# Heater.net
KiCad netlist of a schematic drawn in Altium Designer
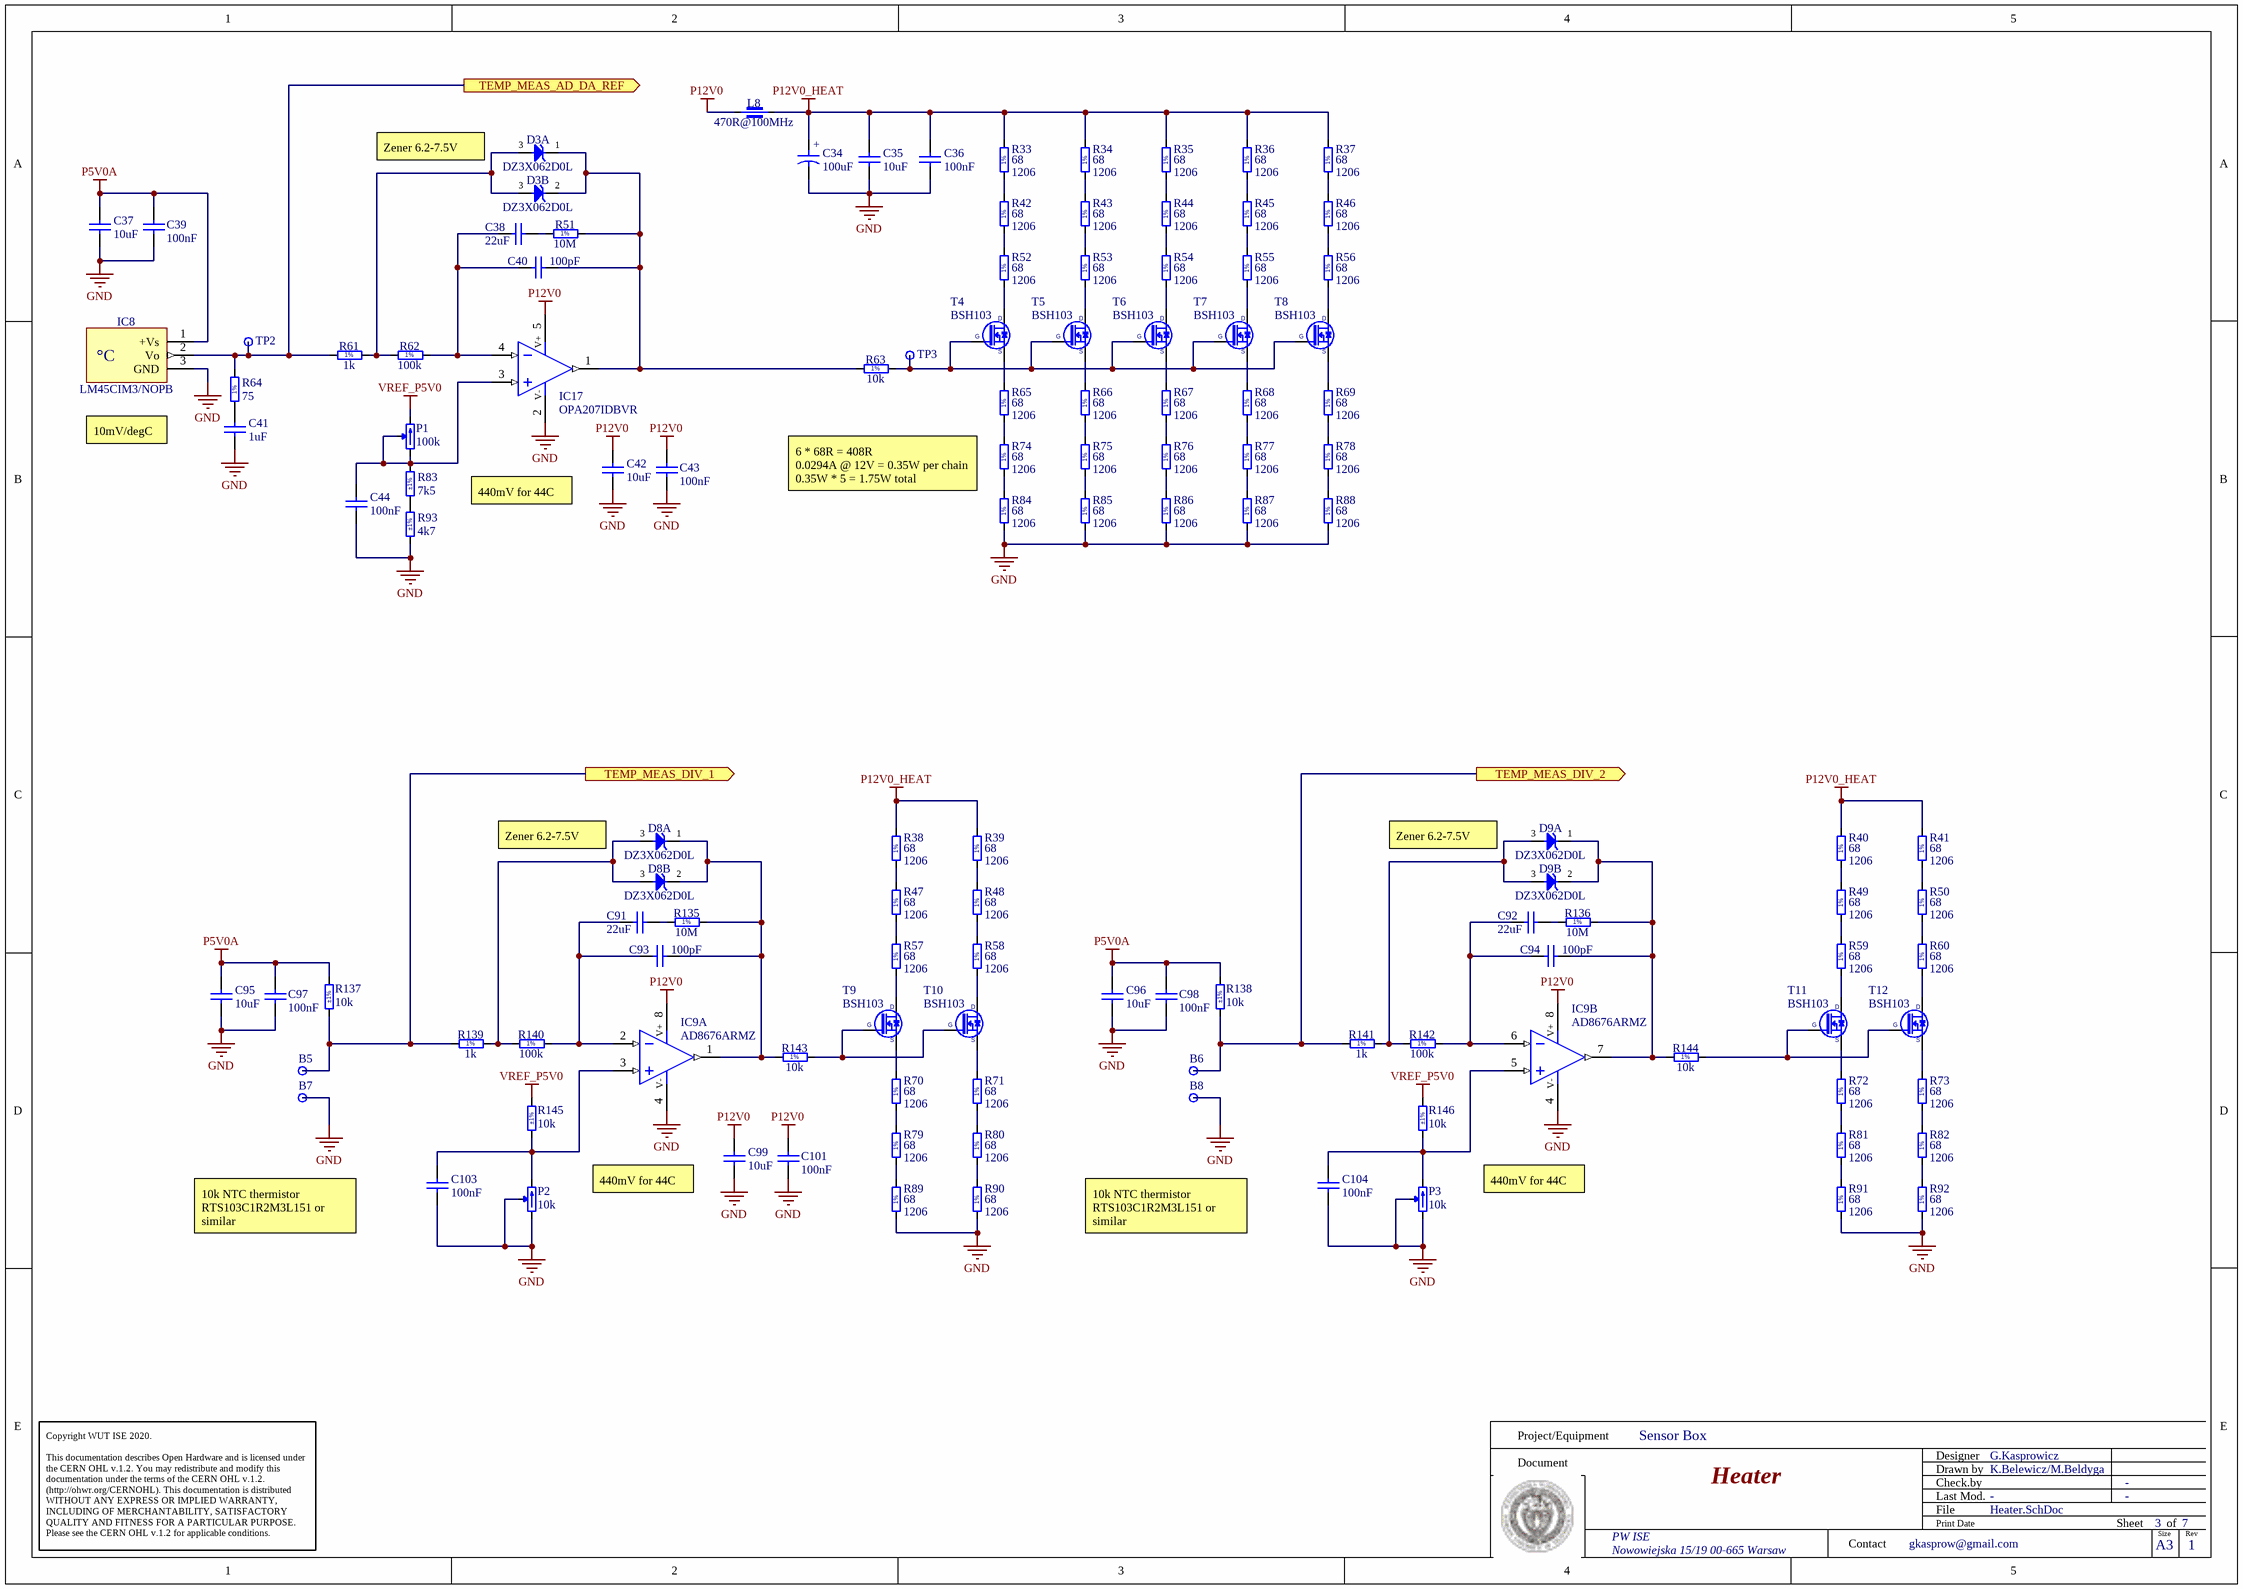
[diagram p0: Heater.SchDoc]

(export (version "E")
  (design (tool "Eeschema 10.0.6"))
  (components
    (comp (ref "B5")
      (value "Plated Hole")
      (footprint "c150h80")
      (description "Single Terminal Socket")
      (fields (field (name "PART NUMBER") "PLATED_HOLE0.8_PAD1.5") (field (name "AUTHOR") "CERN DEM JLC"))
      (libsource (lib "Eletro-mechanical") (part "Single Terminal Socket"))
    )
    (comp (ref "B6")
      (value "Plated Hole")
      (footprint "c150h80")
      (description "Single Terminal Socket")
      (fields (field (name "PART NUMBER") "PLATED_HOLE0.8_PAD1.5") (field (name "AUTHOR") "CERN DEM JLC"))
      (libsource (lib "Eletro-mechanical") (part "Single Terminal Socket"))
    )
    (comp (ref "B7")
      (value "Plated Hole")
      (footprint "c150h80")
      (description "Single Terminal Socket")
      (fields (field (name "PART NUMBER") "PLATED_HOLE0.8_PAD1.5") (field (name "AUTHOR") "CERN DEM JLC"))
      (libsource (lib "Eletro-mechanical") (part "Single Terminal Socket"))
    )
    (comp (ref "B8")
      (value "Plated Hole")
      (footprint "c150h80")
      (description "Single Terminal Socket")
      (fields (field (name "PART NUMBER") "PLATED_HOLE0.8_PAD1.5") (field (name "AUTHOR") "CERN DEM JLC"))
      (libsource (lib "Eletro-mechanical") (part "Single Terminal Socket"))
    )
    (comp (ref "C34")
      (value "100uF")
      (footprint "CAPMP7343X310N")
      (description "Polarised capacitor")
      (fields
        (field (name "PART NUMBER") "CTE7343-31_100UF_20V_10%")
        (field (name "VOLTAGE") "20V")
        (field (name "AUTHOR") "CERN DEM JLC")
      )
      (libsource (lib "Capacitors") (part "Capacitor - polarized"))
    )
    (comp (ref "C35")
      (value "10uF")
      (footprint "CAPC1608X80N")
      (description "Non-polarised capacitor")
      (fields
        (field (name "PART NUMBER") "CC0603_10UF_10V_10%_X5R")
        (field (name "VOLTAGE") "10V")
        (field (name "AUTHOR") "CERN DEM JLC")
      )
      (libsource (lib "Capacitors") (part "Capacitor - non polarized"))
    )
    (comp (ref "C36")
      (value "100nF")
      (footprint "CAPC1005X55N")
      (description "Non-polarised capacitor")
      (fields
        (field (name "PART NUMBER") "CC0402_100NF_16V_10%_X5R")
        (field (name "VOLTAGE") "16V")
        (field (name "AUTHOR") "CERN DEM JLC")
      )
      (libsource (lib "Capacitors") (part "Capacitor - non polarized"))
    )
    (comp (ref "C37")
      (value "10uF")
      (footprint "CAPC1608X80N")
      (description "Non-polarised capacitor")
      (fields
        (field (name "PART NUMBER") "CC0603_10UF_10V_10%_X5R")
        (field (name "VOLTAGE") "10V")
        (field (name "AUTHOR") "CERN DEM JLC")
      )
      (libsource (lib "Capacitors") (part "Capacitor - non polarized"))
    )
    (comp (ref "C38")
      (value "22uF")
      (footprint "CAPC2012X135N")
      (description "Non-polarised capacitor")
      (fields
        (field (name "MANUFACTURER PART NUMBER") "CC0805_22UF_16V_10%_X5R")
        (field (name "MANUFACTURER") "GENERIC")
        (field (name "AUTHOR") "CERN DEM JLC")
      )
      (libsource (lib "Capacitors") (part "Capacitor - non polarized"))
    )
    (comp (ref "C39")
      (value "100nF")
      (footprint "CAPC1005X55N")
      (description "Non-polarised capacitor")
      (fields
        (field (name "PART NUMBER") "CC0402_100NF_50V_10%_X7R")
        (field (name "VOLTAGE") "50V")
        (field (name "AUTHOR") "CERN DEM MR")
      )
      (libsource (lib "Capacitors") (part "Capacitor - non polarized"))
    )
    (comp (ref "C40")
      (value "100pF")
      (footprint "CAPC1005X55N")
      (description "Non-polarised capacitor")
      (fields
        (field (name "PART NUMBER") "CC0402_100PF_50V_5%_C0G")
        (field (name "VOLTAGE") "50V")
        (field (name "AUTHOR") "CERN DEM JLC")
      )
      (libsource (lib "Capacitors") (part "Capacitor - non polarized"))
    )
    (comp (ref "C41")
      (value "1uF")
      (footprint "CAPC1005X55N")
      (description "Non-polarised capacitor")
      (fields
        (field (name "PART NUMBER") "CC0402_1UF_16V_10%_X5R")
        (field (name "VOLTAGE") "16V")
        (field (name "AUTHOR") "CERN DEM JLC")
      )
      (libsource (lib "Capacitors") (part "Capacitor - non polarized"))
    )
    (comp (ref "C42")
      (value "10uF")
      (footprint "CAPC1608X80N")
      (description "Non-polarised capacitor")
      (fields
        (field (name "PART NUMBER") "CC0603_10UF_10V_10%_X5R")
        (field (name "VOLTAGE") "10V")
        (field (name "AUTHOR") "CERN DEM JLC")
      )
      (libsource (lib "Capacitors") (part "Capacitor - non polarized"))
    )
    (comp (ref "C43")
      (value "100nF")
      (footprint "CAPC1005X55N")
      (description "Non-polarised capacitor")
      (fields
        (field (name "PART NUMBER") "CC0402_100NF_50V_10%_X7R")
        (field (name "VOLTAGE") "50V")
        (field (name "AUTHOR") "CERN DEM MR")
      )
      (libsource (lib "Capacitors") (part "Capacitor - non polarized"))
    )
    (comp (ref "C44")
      (value "100nF")
      (footprint "CAPC1005X55N")
      (description "Non-polarised capacitor")
      (fields
        (field (name "PART NUMBER") "CC0402_100NF_16V_10%_X5R")
        (field (name "VOLTAGE") "16V")
        (field (name "AUTHOR") "CERN DEM JLC")
      )
      (libsource (lib "Capacitors") (part "Capacitor - non polarized"))
    )
    (comp (ref "C91")
      (value "22uF")
      (footprint "CAPC2012X135N")
      (description "Non-polarised capacitor")
      (fields
        (field (name "MANUFACTURER PART NUMBER") "CC0805_22UF_16V_10%_X5R")
        (field (name "MANUFACTURER") "GENERIC")
        (field (name "AUTHOR") "CERN DEM JLC")
      )
      (libsource (lib "Capacitors") (part "Capacitor - non polarized"))
    )
    (comp (ref "C92")
      (value "22uF")
      (footprint "CAPC2012X135N")
      (description "Non-polarised capacitor")
      (fields
        (field (name "MANUFACTURER PART NUMBER") "CC0805_22UF_16V_10%_X5R")
        (field (name "MANUFACTURER") "GENERIC")
        (field (name "AUTHOR") "CERN DEM JLC")
      )
      (libsource (lib "Capacitors") (part "Capacitor - non polarized"))
    )
    (comp (ref "C93")
      (value "100pF")
      (footprint "CAPC1005X55N")
      (description "Non-polarised capacitor")
      (fields
        (field (name "PART NUMBER") "CC0402_100PF_50V_5%_C0G")
        (field (name "VOLTAGE") "50V")
        (field (name "AUTHOR") "CERN DEM JLC")
      )
      (libsource (lib "Capacitors") (part "Capacitor - non polarized"))
    )
    (comp (ref "C94")
      (value "100pF")
      (footprint "CAPC1005X55N")
      (description "Non-polarised capacitor")
      (fields
        (field (name "PART NUMBER") "CC0402_100PF_50V_5%_C0G")
        (field (name "VOLTAGE") "50V")
        (field (name "AUTHOR") "CERN DEM JLC")
      )
      (libsource (lib "Capacitors") (part "Capacitor - non polarized"))
    )
    (comp (ref "C95")
      (value "10uF")
      (footprint "CAPC1608X80N")
      (description "Non-polarised capacitor")
      (fields
        (field (name "PART NUMBER") "CC0603_10UF_10V_10%_X5R")
        (field (name "VOLTAGE") "10V")
        (field (name "AUTHOR") "CERN DEM JLC")
      )
      (libsource (lib "Capacitors") (part "Capacitor - non polarized"))
    )
    (comp (ref "C96")
      (value "10uF")
      (footprint "CAPC1608X80N")
      (description "Non-polarised capacitor")
      (fields
        (field (name "PART NUMBER") "CC0603_10UF_10V_10%_X5R")
        (field (name "VOLTAGE") "10V")
        (field (name "AUTHOR") "CERN DEM JLC")
      )
      (libsource (lib "Capacitors") (part "Capacitor - non polarized"))
    )
    (comp (ref "C97")
      (value "100nF")
      (footprint "CAPC1005X55N")
      (description "Non-polarised capacitor")
      (fields
        (field (name "PART NUMBER") "CC0402_100NF_50V_10%_X7R")
        (field (name "VOLTAGE") "50V")
        (field (name "AUTHOR") "CERN DEM MR")
      )
      (libsource (lib "Capacitors") (part "Capacitor - non polarized"))
    )
    (comp (ref "C98")
      (value "100nF")
      (footprint "CAPC1005X55N")
      (description "Non-polarised capacitor")
      (fields
        (field (name "PART NUMBER") "CC0402_100NF_50V_10%_X7R")
        (field (name "VOLTAGE") "50V")
        (field (name "AUTHOR") "CERN DEM MR")
      )
      (libsource (lib "Capacitors") (part "Capacitor - non polarized"))
    )
    (comp (ref "C99")
      (value "10uF")
      (footprint "CAPC1608X80N")
      (description "Non-polarised capacitor")
      (fields
        (field (name "PART NUMBER") "CC0603_10UF_10V_10%_X5R")
        (field (name "VOLTAGE") "10V")
        (field (name "AUTHOR") "CERN DEM JLC")
      )
      (libsource (lib "Capacitors") (part "Capacitor - non polarized"))
    )
    (comp (ref "C101")
      (value "100nF")
      (footprint "CAPC1005X55N")
      (description "Non-polarised capacitor")
      (fields
        (field (name "PART NUMBER") "CC0402_100NF_50V_10%_X7R")
        (field (name "VOLTAGE") "50V")
        (field (name "AUTHOR") "CERN DEM MR")
      )
      (libsource (lib "Capacitors") (part "Capacitor - non polarized"))
    )
    (comp (ref "C103")
      (value "100nF")
      (footprint "CAPC1005X55N")
      (description "Non-polarised capacitor")
      (fields
        (field (name "PART NUMBER") "CC0402_100NF_16V_10%_X5R")
        (field (name "VOLTAGE") "16V")
        (field (name "AUTHOR") "CERN DEM JLC")
      )
      (libsource (lib "Capacitors") (part "Capacitor - non polarized"))
    )
    (comp (ref "C104")
      (value "100nF")
      (footprint "CAPC1005X55N")
      (description "Non-polarised capacitor")
      (fields
        (field (name "PART NUMBER") "CC0402_100NF_16V_10%_X5R")
        (field (name "VOLTAGE") "16V")
        (field (name "AUTHOR") "CERN DEM JLC")
      )
      (libsource (lib "Capacitors") (part "Capacitor - non polarized"))
    )
    (comp (ref "D3")
      (value "DZ3X062D0L")
      (footprint "SOT95P275X140-3N")
      (description "Dual Common Anode Zener Diode")
      (fields
        (field (name "VOLTAGE") "6.2V")
        (field (name "POWER") "200mA")
        (field (name "AUTHOR") "CERN DEM JLC")
      )
      (libsource (lib "ICs And Semiconductors") (part "Diode Zener x2 C1A3_C2A3"))
    )
    (comp (ref "D8")
      (value "DZ3X062D0L")
      (footprint "SOT95P275X140-3N")
      (description "Dual Common Anode Zener Diode")
      (fields
        (field (name "VOLTAGE") "6.2V")
        (field (name "POWER") "200mA")
        (field (name "AUTHOR") "CERN DEM JLC")
      )
      (libsource (lib "ICs And Semiconductors") (part "Diode Zener x2 C1A3_C2A3"))
    )
    (comp (ref "D9")
      (value "DZ3X062D0L")
      (footprint "SOT95P275X140-3N")
      (description "Dual Common Anode Zener Diode")
      (fields
        (field (name "VOLTAGE") "6.2V")
        (field (name "POWER") "200mA")
        (field (name "AUTHOR") "CERN DEM JLC")
      )
      (libsource (lib "ICs And Semiconductors") (part "Diode Zener x2 C1A3_C2A3"))
    )
    (comp (ref "IC8")
      (value "LM45CIM3/NOPB")
      (footprint "SOT95P251X112-3N")
      (description "-20° to +100°C ±3°C Precision Centigrade Temperature Sensors")
      (fields (field (name "MANUFACTURER") "TEXAS INSTRUMENTS") (field (name "AUTHOR") "CERN DEM JLC"))
      (libsource (lib "ICs And Semiconductors") (part "LM45"))
    )
    (comp (ref "IC9")
      (value "AD8676ARMZ")
      (footprint "SOP65P490X110-8N")
      (description "Dual Operational Amplifier")
      (fields
        (field (name "MANUFACTURER") "ANALOG DEVICES")
        (field (name "MANUFACTURER PART NUMBER") "AD8676ARM")
        (field (name "AUTHOR") "CERN DEM JLC")
      )
      (libsource (lib "ICs And Semiconductors") (part "Operational Amplifier x2 Type1"))
    )
    (comp (ref "IC17")
      (value "OPA207IDBVR")
      (footprint "SOT95P280X145-5N")
      (description "2.2nV/sqrt Hz, Low-Power, 36-V Operational Amplifier")
      (fields (field (name "MANUFACTURER") "TEXAS INSTRUMENTS"))
      (libsource (lib "Operational Amplifiers") (part "OPA207IDBVR"))
    )
    (comp (ref "L8")
      (value "470R@100MHz")
      (footprint "INDC1608X95N")
      (fields
        (field (name "PART NUMBER") "IND0603_MURATA_BLM18PG471SN1D")
        (field (name "POWER") "1A")
        (field (name "TOLERANCE") "±25%")
        (field (name "AUTHOR") "CERN DEM BC")
      )
      (libsource (lib "Inductors & Transformers") (part "Ferrite Bead"))
    )
    (comp (ref "P1")
      (value "100k")
      (footprint "TRIM_BOURNS_3224X")
      (description "Trimming Potentiometer")
      (fields
        (field (name "PART NUMBER") "TRIM_12T_100K_BOURNS_3224X-1-104E")
        (field (name "POWER") "0.25W")
        (field (name "AUTHOR") "CERN DEM JLC")
      )
      (libsource (lib "Resistors") (part "Trimming Potentiometer"))
    )
    (comp (ref "P2")
      (value "10k")
      (footprint "TRIM_BOURNS_3224X")
      (description "Trimming Potentiometer")
      (fields
        (field (name "PART NUMBER") "TRIM_12T_10K_BOURNS_3224X-1-103E")
        (field (name "POWER") "0.25W")
        (field (name "AUTHOR") "CERN DEM JLC")
      )
      (libsource (lib "Resistors") (part "Trimming Potentiometer"))
    )
    (comp (ref "P3")
      (value "10k")
      (footprint "TRIM_BOURNS_3224X")
      (description "Trimming Potentiometer")
      (fields
        (field (name "PART NUMBER") "TRIM_12T_10K_BOURNS_3224X-1-103E")
        (field (name "POWER") "0.25W")
        (field (name "AUTHOR") "CERN DEM JLC")
      )
      (libsource (lib "Resistors") (part "Trimming Potentiometer"))
    )
    (comp (ref "R33")
      (value "68")
      (footprint "RESC3216X65N")
      (description "Resistor - 1%")
      (fields
        (field (name "PART NUMBER") "R1206_68R_1%_0.25W_100PPM")
        (field (name "POWER") "0.25W")
        (field (name "CASE") "1206")
        (field (name "AUTHOR") "CERN DEM JLC")
      )
      (libsource (lib "Resistors") (part "Resistor - 1%"))
    )
    (comp (ref "R34")
      (value "68")
      (footprint "RESC3216X65N")
      (description "Resistor - 1%")
      (fields
        (field (name "PART NUMBER") "R1206_68R_1%_0.25W_100PPM")
        (field (name "POWER") "0.25W")
        (field (name "CASE") "1206")
        (field (name "AUTHOR") "CERN DEM JLC")
      )
      (libsource (lib "Resistors") (part "Resistor - 1%"))
    )
    (comp (ref "R35")
      (value "68")
      (footprint "RESC3216X65N")
      (description "Resistor - 1%")
      (fields
        (field (name "PART NUMBER") "R1206_68R_1%_0.25W_100PPM")
        (field (name "POWER") "0.25W")
        (field (name "CASE") "1206")
        (field (name "AUTHOR") "CERN DEM JLC")
      )
      (libsource (lib "Resistors") (part "Resistor - 1%"))
    )
    (comp (ref "R36")
      (value "68")
      (footprint "RESC3216X65N")
      (description "Resistor - 1%")
      (fields
        (field (name "PART NUMBER") "R1206_68R_1%_0.25W_100PPM")
        (field (name "POWER") "0.25W")
        (field (name "CASE") "1206")
        (field (name "AUTHOR") "CERN DEM JLC")
      )
      (libsource (lib "Resistors") (part "Resistor - 1%"))
    )
    (comp (ref "R37")
      (value "68")
      (footprint "RESC3216X65N")
      (description "Resistor - 1%")
      (fields
        (field (name "PART NUMBER") "R1206_68R_1%_0.25W_100PPM")
        (field (name "POWER") "0.25W")
        (field (name "CASE") "1206")
        (field (name "AUTHOR") "CERN DEM JLC")
      )
      (libsource (lib "Resistors") (part "Resistor - 1%"))
    )
    (comp (ref "R38")
      (value "68")
      (footprint "RESC3216X65N")
      (description "Resistor - 1%")
      (fields
        (field (name "PART NUMBER") "R1206_68R_1%_0.25W_100PPM")
        (field (name "POWER") "0.25W")
        (field (name "CASE") "1206")
        (field (name "AUTHOR") "CERN DEM JLC")
      )
      (libsource (lib "Resistors") (part "Resistor - 1%"))
    )
    (comp (ref "R39")
      (value "68")
      (footprint "RESC3216X65N")
      (description "Resistor - 1%")
      (fields
        (field (name "PART NUMBER") "R1206_68R_1%_0.25W_100PPM")
        (field (name "POWER") "0.25W")
        (field (name "CASE") "1206")
        (field (name "AUTHOR") "CERN DEM JLC")
      )
      (libsource (lib "Resistors") (part "Resistor - 1%"))
    )
    (comp (ref "R40")
      (value "68")
      (footprint "RESC3216X65N")
      (description "Resistor - 1%")
      (fields
        (field (name "PART NUMBER") "R1206_68R_1%_0.25W_100PPM")
        (field (name "POWER") "0.25W")
        (field (name "CASE") "1206")
        (field (name "AUTHOR") "CERN DEM JLC")
      )
      (libsource (lib "Resistors") (part "Resistor - 1%"))
    )
    (comp (ref "R41")
      (value "68")
      (footprint "RESC3216X65N")
      (description "Resistor - 1%")
      (fields
        (field (name "PART NUMBER") "R1206_68R_1%_0.25W_100PPM")
        (field (name "POWER") "0.25W")
        (field (name "CASE") "1206")
        (field (name "AUTHOR") "CERN DEM JLC")
      )
      (libsource (lib "Resistors") (part "Resistor - 1%"))
    )
    (comp (ref "R42")
      (value "68")
      (footprint "RESC3216X65N")
      (description "Resistor - 1%")
      (fields
        (field (name "PART NUMBER") "R1206_68R_1%_0.25W_100PPM")
        (field (name "POWER") "0.25W")
        (field (name "CASE") "1206")
        (field (name "AUTHOR") "CERN DEM JLC")
      )
      (libsource (lib "Resistors") (part "Resistor - 1%"))
    )
    (comp (ref "R43")
      (value "68")
      (footprint "RESC3216X65N")
      (description "Resistor - 1%")
      (fields
        (field (name "PART NUMBER") "R1206_68R_1%_0.25W_100PPM")
        (field (name "POWER") "0.25W")
        (field (name "CASE") "1206")
        (field (name "AUTHOR") "CERN DEM JLC")
      )
      (libsource (lib "Resistors") (part "Resistor - 1%"))
    )
    (comp (ref "R44")
      (value "68")
      (footprint "RESC3216X65N")
      (description "Resistor - 1%")
      (fields
        (field (name "PART NUMBER") "R1206_68R_1%_0.25W_100PPM")
        (field (name "POWER") "0.25W")
        (field (name "CASE") "1206")
        (field (name "AUTHOR") "CERN DEM JLC")
      )
      (libsource (lib "Resistors") (part "Resistor - 1%"))
    )
    (comp (ref "R45")
      (value "68")
      (footprint "RESC3216X65N")
      (description "Resistor - 1%")
      (fields
        (field (name "PART NUMBER") "R1206_68R_1%_0.25W_100PPM")
        (field (name "POWER") "0.25W")
        (field (name "CASE") "1206")
        (field (name "AUTHOR") "CERN DEM JLC")
      )
      (libsource (lib "Resistors") (part "Resistor - 1%"))
    )
    (comp (ref "R46")
      (value "68")
      (footprint "RESC3216X65N")
      (description "Resistor - 1%")
      (fields
        (field (name "PART NUMBER") "R1206_68R_1%_0.25W_100PPM")
        (field (name "POWER") "0.25W")
        (field (name "CASE") "1206")
        (field (name "AUTHOR") "CERN DEM JLC")
      )
      (libsource (lib "Resistors") (part "Resistor - 1%"))
    )
    (comp (ref "R47")
      (value "68")
      (footprint "RESC3216X65N")
      (description "Resistor - 1%")
      (fields
        (field (name "PART NUMBER") "R1206_68R_1%_0.25W_100PPM")
        (field (name "POWER") "0.25W")
        (field (name "CASE") "1206")
        (field (name "AUTHOR") "CERN DEM JLC")
      )
      (libsource (lib "Resistors") (part "Resistor - 1%"))
    )
    (comp (ref "R48")
      (value "68")
      (footprint "RESC3216X65N")
      (description "Resistor - 1%")
      (fields
        (field (name "PART NUMBER") "R1206_68R_1%_0.25W_100PPM")
        (field (name "POWER") "0.25W")
        (field (name "CASE") "1206")
        (field (name "AUTHOR") "CERN DEM JLC")
      )
      (libsource (lib "Resistors") (part "Resistor - 1%"))
    )
    (comp (ref "R49")
      (value "68")
      (footprint "RESC3216X65N")
      (description "Resistor - 1%")
      (fields
        (field (name "PART NUMBER") "R1206_68R_1%_0.25W_100PPM")
        (field (name "POWER") "0.25W")
        (field (name "CASE") "1206")
        (field (name "AUTHOR") "CERN DEM JLC")
      )
      (libsource (lib "Resistors") (part "Resistor - 1%"))
    )
    (comp (ref "R50")
      (value "68")
      (footprint "RESC3216X65N")
      (description "Resistor - 1%")
      (fields
        (field (name "PART NUMBER") "R1206_68R_1%_0.25W_100PPM")
        (field (name "POWER") "0.25W")
        (field (name "CASE") "1206")
        (field (name "AUTHOR") "CERN DEM JLC")
      )
      (libsource (lib "Resistors") (part "Resistor - 1%"))
    )
    (comp (ref "R51")
      (value "10M")
      (footprint "RESC2113X55N")
      (description "Resistor - 1%")
      (fields
        (field (name "PART NUMBER") "R0805_10M_1%_0.125W_100PPM_VISHAY_CRCW e3")
        (field (name "POWER") "0.125W")
        (field (name "AUTHOR") "CERN DEM BC")
      )
      (libsource (lib "Resistors") (part "Resistor - 1%"))
    )
    (comp (ref "R52")
      (value "68")
      (footprint "RESC3216X65N")
      (description "Resistor - 1%")
      (fields
        (field (name "PART NUMBER") "R1206_68R_1%_0.25W_100PPM")
        (field (name "POWER") "0.25W")
        (field (name "CASE") "1206")
        (field (name "AUTHOR") "CERN DEM JLC")
      )
      (libsource (lib "Resistors") (part "Resistor - 1%"))
    )
    (comp (ref "R53")
      (value "68")
      (footprint "RESC3216X65N")
      (description "Resistor - 1%")
      (fields
        (field (name "PART NUMBER") "R1206_68R_1%_0.25W_100PPM")
        (field (name "POWER") "0.25W")
        (field (name "CASE") "1206")
        (field (name "AUTHOR") "CERN DEM JLC")
      )
      (libsource (lib "Resistors") (part "Resistor - 1%"))
    )
    (comp (ref "R54")
      (value "68")
      (footprint "RESC3216X65N")
      (description "Resistor - 1%")
      (fields
        (field (name "PART NUMBER") "R1206_68R_1%_0.25W_100PPM")
        (field (name "POWER") "0.25W")
        (field (name "CASE") "1206")
        (field (name "AUTHOR") "CERN DEM JLC")
      )
      (libsource (lib "Resistors") (part "Resistor - 1%"))
    )
    (comp (ref "R55")
      (value "68")
      (footprint "RESC3216X65N")
      (description "Resistor - 1%")
      (fields
        (field (name "PART NUMBER") "R1206_68R_1%_0.25W_100PPM")
        (field (name "POWER") "0.25W")
        (field (name "CASE") "1206")
        (field (name "AUTHOR") "CERN DEM JLC")
      )
      (libsource (lib "Resistors") (part "Resistor - 1%"))
    )
    (comp (ref "R56")
      (value "68")
      (footprint "RESC3216X65N")
      (description "Resistor - 1%")
      (fields
        (field (name "PART NUMBER") "R1206_68R_1%_0.25W_100PPM")
        (field (name "POWER") "0.25W")
        (field (name "CASE") "1206")
        (field (name "AUTHOR") "CERN DEM JLC")
      )
      (libsource (lib "Resistors") (part "Resistor - 1%"))
    )
    (comp (ref "R57")
      (value "68")
      (footprint "RESC3216X65N")
      (description "Resistor - 1%")
      (fields
        (field (name "PART NUMBER") "R1206_68R_1%_0.25W_100PPM")
        (field (name "POWER") "0.25W")
        (field (name "CASE") "1206")
        (field (name "AUTHOR") "CERN DEM JLC")
      )
      (libsource (lib "Resistors") (part "Resistor - 1%"))
    )
    (comp (ref "R58")
      (value "68")
      (footprint "RESC3216X65N")
      (description "Resistor - 1%")
      (fields
        (field (name "PART NUMBER") "R1206_68R_1%_0.25W_100PPM")
        (field (name "POWER") "0.25W")
        (field (name "CASE") "1206")
        (field (name "AUTHOR") "CERN DEM JLC")
      )
      (libsource (lib "Resistors") (part "Resistor - 1%"))
    )
    (comp (ref "R59")
      (value "68")
      (footprint "RESC3216X65N")
      (description "Resistor - 1%")
      (fields
        (field (name "PART NUMBER") "R1206_68R_1%_0.25W_100PPM")
        (field (name "POWER") "0.25W")
        (field (name "CASE") "1206")
        (field (name "AUTHOR") "CERN DEM JLC")
      )
      (libsource (lib "Resistors") (part "Resistor - 1%"))
    )
    (comp (ref "R60")
      (value "68")
      (footprint "RESC3216X65N")
      (description "Resistor - 1%")
      (fields
        (field (name "PART NUMBER") "R1206_68R_1%_0.25W_100PPM")
        (field (name "POWER") "0.25W")
        (field (name "CASE") "1206")
        (field (name "AUTHOR") "CERN DEM JLC")
      )
      (libsource (lib "Resistors") (part "Resistor - 1%"))
    )
    (comp (ref "R61")
      (value "1k")
      (footprint "RESC1005X40N")
      (description "Resistor - 1%")
      (fields
        (field (name "PART NUMBER") "R0402_1K_1%_0.0625W_100PPM")
        (field (name "POWER") "0.0625W")
        (field (name "AUTHOR") "CERN DEM JLC")
      )
      (libsource (lib "") (part "Resistor - 1%_1"))
    )
    (comp (ref "R62")
      (value "100k")
      (footprint "RESC1005X40N")
      (description "Resistor - 1%")
      (fields
        (field (name "PART NUMBER") "R0402_100K_1%_0.0625W_100PPM")
        (field (name "POWER") "0.0625W")
        (field (name "AUTHOR") "CERN DEM JLC")
      )
      (libsource (lib "") (part "Resistor - 1%_1"))
    )
    (comp (ref "R63")
      (value "10k")
      (footprint "RESC1005X40N")
      (description "Resistor - 1%")
      (fields
        (field (name "PART NUMBER") "R0402_10K_1%_0.0625W_100PPM")
        (field (name "POWER") "0.0625W")
        (field (name "AUTHOR") "CERN DEM JLC")
      )
      (libsource (lib "") (part "Resistor - 1%_1"))
    )
    (comp (ref "R64")
      (value "75")
      (footprint "RESC1005X40N")
      (description "Resistor - 1%")
      (fields
        (field (name "PART NUMBER") "R0402_75R_1%_0.0625W_100PPM")
        (field (name "POWER") "0.0625W")
        (field (name "AUTHOR") "CERN DEM JLC")
      )
      (libsource (lib "") (part "Resistor - 1%_1"))
    )
    (comp (ref "R65")
      (value "68")
      (footprint "RESC3216X65N")
      (description "Resistor - 1%")
      (fields
        (field (name "PART NUMBER") "R1206_68R_1%_0.25W_100PPM")
        (field (name "POWER") "0.25W")
        (field (name "CASE") "1206")
        (field (name "AUTHOR") "CERN DEM JLC")
      )
      (libsource (lib "Resistors") (part "Resistor - 1%"))
    )
    (comp (ref "R66")
      (value "68")
      (footprint "RESC3216X65N")
      (description "Resistor - 1%")
      (fields
        (field (name "PART NUMBER") "R1206_68R_1%_0.25W_100PPM")
        (field (name "POWER") "0.25W")
        (field (name "CASE") "1206")
        (field (name "AUTHOR") "CERN DEM JLC")
      )
      (libsource (lib "Resistors") (part "Resistor - 1%"))
    )
    (comp (ref "R67")
      (value "68")
      (footprint "RESC3216X65N")
      (description "Resistor - 1%")
      (fields
        (field (name "PART NUMBER") "R1206_68R_1%_0.25W_100PPM")
        (field (name "POWER") "0.25W")
        (field (name "CASE") "1206")
        (field (name "AUTHOR") "CERN DEM JLC")
      )
      (libsource (lib "Resistors") (part "Resistor - 1%"))
    )
    (comp (ref "R68")
      (value "68")
      (footprint "RESC3216X65N")
      (description "Resistor - 1%")
      (fields
        (field (name "PART NUMBER") "R1206_68R_1%_0.25W_100PPM")
        (field (name "POWER") "0.25W")
        (field (name "CASE") "1206")
        (field (name "AUTHOR") "CERN DEM JLC")
      )
      (libsource (lib "Resistors") (part "Resistor - 1%"))
    )
    (comp (ref "R69")
      (value "68")
      (footprint "RESC3216X65N")
      (description "Resistor - 1%")
      (fields
        (field (name "PART NUMBER") "R1206_68R_1%_0.25W_100PPM")
        (field (name "POWER") "0.25W")
        (field (name "CASE") "1206")
        (field (name "AUTHOR") "CERN DEM JLC")
      )
      (libsource (lib "Resistors") (part "Resistor - 1%"))
    )
    (comp (ref "R70")
      (value "68")
      (footprint "RESC3216X65N")
      (description "Resistor - 1%")
      (fields
        (field (name "PART NUMBER") "R1206_68R_1%_0.25W_100PPM")
        (field (name "POWER") "0.25W")
        (field (name "CASE") "1206")
        (field (name "AUTHOR") "CERN DEM JLC")
      )
      (libsource (lib "Resistors") (part "Resistor - 1%"))
    )
    (comp (ref "R71")
      (value "68")
      (footprint "RESC3216X65N")
      (description "Resistor - 1%")
      (fields
        (field (name "PART NUMBER") "R1206_68R_1%_0.25W_100PPM")
        (field (name "POWER") "0.25W")
        (field (name "CASE") "1206")
        (field (name "AUTHOR") "CERN DEM JLC")
      )
      (libsource (lib "Resistors") (part "Resistor - 1%"))
    )
    (comp (ref "R72")
      (value "68")
      (footprint "RESC3216X65N")
      (description "Resistor - 1%")
      (fields
        (field (name "PART NUMBER") "R1206_68R_1%_0.25W_100PPM")
        (field (name "POWER") "0.25W")
        (field (name "CASE") "1206")
        (field (name "AUTHOR") "CERN DEM JLC")
      )
      (libsource (lib "Resistors") (part "Resistor - 1%"))
    )
    (comp (ref "R73")
      (value "68")
      (footprint "RESC3216X65N")
      (description "Resistor - 1%")
      (fields
        (field (name "PART NUMBER") "R1206_68R_1%_0.25W_100PPM")
        (field (name "POWER") "0.25W")
        (field (name "CASE") "1206")
        (field (name "AUTHOR") "CERN DEM JLC")
      )
      (libsource (lib "Resistors") (part "Resistor - 1%"))
    )
    (comp (ref "R74")
      (value "68")
      (footprint "RESC3216X65N")
      (description "Resistor - 1%")
      (fields
        (field (name "PART NUMBER") "R1206_68R_1%_0.25W_100PPM")
        (field (name "POWER") "0.25W")
        (field (name "CASE") "1206")
        (field (name "AUTHOR") "CERN DEM JLC")
      )
      (libsource (lib "Resistors") (part "Resistor - 1%"))
    )
    (comp (ref "R75")
      (value "68")
      (footprint "RESC3216X65N")
      (description "Resistor - 1%")
      (fields
        (field (name "PART NUMBER") "R1206_68R_1%_0.25W_100PPM")
        (field (name "POWER") "0.25W")
        (field (name "CASE") "1206")
        (field (name "AUTHOR") "CERN DEM JLC")
      )
      (libsource (lib "Resistors") (part "Resistor - 1%"))
    )
    (comp (ref "R76")
      (value "68")
      (footprint "RESC3216X65N")
      (description "Resistor - 1%")
      (fields
        (field (name "PART NUMBER") "R1206_68R_1%_0.25W_100PPM")
        (field (name "POWER") "0.25W")
        (field (name "CASE") "1206")
        (field (name "AUTHOR") "CERN DEM JLC")
      )
      (libsource (lib "Resistors") (part "Resistor - 1%"))
    )
    (comp (ref "R77")
      (value "68")
      (footprint "RESC3216X65N")
      (description "Resistor - 1%")
      (fields
        (field (name "PART NUMBER") "R1206_68R_1%_0.25W_100PPM")
        (field (name "POWER") "0.25W")
        (field (name "CASE") "1206")
        (field (name "AUTHOR") "CERN DEM JLC")
      )
      (libsource (lib "Resistors") (part "Resistor - 1%"))
    )
    (comp (ref "R78")
      (value "68")
      (footprint "RESC3216X65N")
      (description "Resistor - 1%")
      (fields
        (field (name "PART NUMBER") "R1206_68R_1%_0.25W_100PPM")
        (field (name "POWER") "0.25W")
        (field (name "CASE") "1206")
        (field (name "AUTHOR") "CERN DEM JLC")
      )
      (libsource (lib "Resistors") (part "Resistor - 1%"))
    )
    (comp (ref "R79")
      (value "68")
      (footprint "RESC3216X65N")
      (description "Resistor - 1%")
      (fields
        (field (name "PART NUMBER") "R1206_68R_1%_0.25W_100PPM")
        (field (name "POWER") "0.25W")
        (field (name "CASE") "1206")
        (field (name "AUTHOR") "CERN DEM JLC")
      )
      (libsource (lib "Resistors") (part "Resistor - 1%"))
    )
    (comp (ref "R80")
      (value "68")
      (footprint "RESC3216X65N")
      (description "Resistor - 1%")
      (fields
        (field (name "PART NUMBER") "R1206_68R_1%_0.25W_100PPM")
        (field (name "POWER") "0.25W")
        (field (name "CASE") "1206")
        (field (name "AUTHOR") "CERN DEM JLC")
      )
      (libsource (lib "Resistors") (part "Resistor - 1%"))
    )
    (comp (ref "R81")
      (value "68")
      (footprint "RESC3216X65N")
      (description "Resistor - 1%")
      (fields
        (field (name "PART NUMBER") "R1206_68R_1%_0.25W_100PPM")
        (field (name "POWER") "0.25W")
        (field (name "CASE") "1206")
        (field (name "AUTHOR") "CERN DEM JLC")
      )
      (libsource (lib "Resistors") (part "Resistor - 1%"))
    )
    (comp (ref "R82")
      (value "68")
      (footprint "RESC3216X65N")
      (description "Resistor - 1%")
      (fields
        (field (name "PART NUMBER") "R1206_68R_1%_0.25W_100PPM")
        (field (name "POWER") "0.25W")
        (field (name "CASE") "1206")
        (field (name "AUTHOR") "CERN DEM JLC")
      )
      (libsource (lib "Resistors") (part "Resistor - 1%"))
    )
    (comp (ref "R83")
      (value "7k5")
      (footprint "RESC1005X40N")
      (description "Resistor - 1%")
      (fields
        (field (name "TOLERANCE") "±1%")
        (field (name "PART NUMBER") "R0402_7K5_1%_0.0625W_100PPM")
        (field (name "POWER") "0.0625W")
        (field (name "AUTHOR") "CERN DEM JLC")
      )
      (libsource (lib "") (part "Resistor - 1%_1"))
    )
    (comp (ref "R84")
      (value "68")
      (footprint "RESC3216X65N")
      (description "Resistor - 1%")
      (fields
        (field (name "PART NUMBER") "R1206_68R_1%_0.25W_100PPM")
        (field (name "POWER") "0.25W")
        (field (name "CASE") "1206")
        (field (name "AUTHOR") "CERN DEM JLC")
      )
      (libsource (lib "Resistors") (part "Resistor - 1%"))
    )
    (comp (ref "R85")
      (value "68")
      (footprint "RESC3216X65N")
      (description "Resistor - 1%")
      (fields
        (field (name "PART NUMBER") "R1206_68R_1%_0.25W_100PPM")
        (field (name "POWER") "0.25W")
        (field (name "CASE") "1206")
        (field (name "AUTHOR") "CERN DEM JLC")
      )
      (libsource (lib "Resistors") (part "Resistor - 1%"))
    )
    (comp (ref "R86")
      (value "68")
      (footprint "RESC3216X65N")
      (description "Resistor - 1%")
      (fields
        (field (name "PART NUMBER") "R1206_68R_1%_0.25W_100PPM")
        (field (name "POWER") "0.25W")
        (field (name "CASE") "1206")
        (field (name "AUTHOR") "CERN DEM JLC")
      )
      (libsource (lib "Resistors") (part "Resistor - 1%"))
    )
    (comp (ref "R87")
      (value "68")
      (footprint "RESC3216X65N")
      (description "Resistor - 1%")
      (fields
        (field (name "PART NUMBER") "R1206_68R_1%_0.25W_100PPM")
        (field (name "POWER") "0.25W")
        (field (name "CASE") "1206")
        (field (name "AUTHOR") "CERN DEM JLC")
      )
      (libsource (lib "Resistors") (part "Resistor - 1%"))
    )
    (comp (ref "R88")
      (value "68")
      (footprint "RESC3216X65N")
      (description "Resistor - 1%")
      (fields
        (field (name "PART NUMBER") "R1206_68R_1%_0.25W_100PPM")
        (field (name "POWER") "0.25W")
        (field (name "CASE") "1206")
        (field (name "AUTHOR") "CERN DEM JLC")
      )
      (libsource (lib "Resistors") (part "Resistor - 1%"))
    )
    (comp (ref "R89")
      (value "68")
      (footprint "RESC3216X65N")
      (description "Resistor - 1%")
      (fields
        (field (name "PART NUMBER") "R1206_68R_1%_0.25W_100PPM")
        (field (name "POWER") "0.25W")
        (field (name "CASE") "1206")
        (field (name "AUTHOR") "CERN DEM JLC")
      )
      (libsource (lib "Resistors") (part "Resistor - 1%"))
    )
    (comp (ref "R90")
      (value "68")
      (footprint "RESC3216X65N")
      (description "Resistor - 1%")
      (fields
        (field (name "PART NUMBER") "R1206_68R_1%_0.25W_100PPM")
        (field (name "POWER") "0.25W")
        (field (name "CASE") "1206")
        (field (name "AUTHOR") "CERN DEM JLC")
      )
      (libsource (lib "Resistors") (part "Resistor - 1%"))
    )
    (comp (ref "R91")
      (value "68")
      (footprint "RESC3216X65N")
      (description "Resistor - 1%")
      (fields
        (field (name "PART NUMBER") "R1206_68R_1%_0.25W_100PPM")
        (field (name "POWER") "0.25W")
        (field (name "CASE") "1206")
        (field (name "AUTHOR") "CERN DEM JLC")
      )
      (libsource (lib "Resistors") (part "Resistor - 1%"))
    )
    (comp (ref "R92")
      (value "68")
      (footprint "RESC3216X65N")
      (description "Resistor - 1%")
      (fields
        (field (name "PART NUMBER") "R1206_68R_1%_0.25W_100PPM")
        (field (name "POWER") "0.25W")
        (field (name "CASE") "1206")
        (field (name "AUTHOR") "CERN DEM JLC")
      )
      (libsource (lib "Resistors") (part "Resistor - 1%"))
    )
    (comp (ref "R93")
      (value "4k7")
      (footprint "RESC1005X40N")
      (description "Resistor - 1%")
      (fields
        (field (name "TOLERANCE") "±1%")
        (field (name "PART NUMBER") "R0402_4K7_1%_0.0625W_100PPM")
        (field (name "POWER") "0.0625W")
        (field (name "AUTHOR") "CERN DEM JLC")
      )
      (libsource (lib "") (part "Resistor - 1%_1"))
    )
    (comp (ref "R135")
      (value "10M")
      (footprint "RESC2113X55N")
      (description "Resistor - 1%")
      (fields
        (field (name "PART NUMBER") "R0805_10M_1%_0.125W_100PPM_VISHAY_CRCW e3")
        (field (name "POWER") "0.125W")
        (field (name "AUTHOR") "CERN DEM BC")
      )
      (libsource (lib "Resistors") (part "Resistor - 1%"))
    )
    (comp (ref "R136")
      (value "10M")
      (footprint "RESC2113X55N")
      (description "Resistor - 1%")
      (fields
        (field (name "PART NUMBER") "R0805_10M_1%_0.125W_100PPM_VISHAY_CRCW e3")
        (field (name "POWER") "0.125W")
        (field (name "AUTHOR") "CERN DEM BC")
      )
      (libsource (lib "Resistors") (part "Resistor - 1%"))
    )
    (comp (ref "R137")
      (value "10k")
      (footprint "RESC1005X40N")
      (description "Resistor - 1%")
      (fields
        (field (name "TOLERANCE") "±1%")
        (field (name "PART NUMBER") "R0402_10K_1%_0.0625W_100PPM")
        (field (name "POWER") "0.0625W")
        (field (name "AUTHOR") "CERN DEM JLC")
      )
      (libsource (lib "") (part "Resistor - 1%_1"))
    )
    (comp (ref "R138")
      (value "10k")
      (footprint "RESC1005X40N")
      (description "Resistor - 1%")
      (fields
        (field (name "TOLERANCE") "±1%")
        (field (name "PART NUMBER") "R0402_10K_1%_0.0625W_100PPM")
        (field (name "POWER") "0.0625W")
        (field (name "AUTHOR") "CERN DEM JLC")
      )
      (libsource (lib "") (part "Resistor - 1%_1"))
    )
    (comp (ref "R139")
      (value "1k")
      (footprint "RESC1005X40N")
      (description "Resistor - 1%")
      (fields
        (field (name "PART NUMBER") "R0402_1K_1%_0.0625W_100PPM")
        (field (name "POWER") "0.0625W")
        (field (name "AUTHOR") "CERN DEM JLC")
      )
      (libsource (lib "") (part "Resistor - 1%_1"))
    )
    (comp (ref "R140")
      (value "100k")
      (footprint "RESC1005X40N")
      (description "Resistor - 1%")
      (fields
        (field (name "PART NUMBER") "R0402_100K_1%_0.0625W_100PPM")
        (field (name "POWER") "0.0625W")
        (field (name "AUTHOR") "CERN DEM JLC")
      )
      (libsource (lib "") (part "Resistor - 1%_1"))
    )
    (comp (ref "R141")
      (value "1k")
      (footprint "RESC1005X40N")
      (description "Resistor - 1%")
      (fields
        (field (name "PART NUMBER") "R0402_1K_1%_0.0625W_100PPM")
        (field (name "POWER") "0.0625W")
        (field (name "AUTHOR") "CERN DEM JLC")
      )
      (libsource (lib "") (part "Resistor - 1%_1"))
    )
    (comp (ref "R142")
      (value "100k")
      (footprint "RESC1005X40N")
      (description "Resistor - 1%")
      (fields
        (field (name "PART NUMBER") "R0402_100K_1%_0.0625W_100PPM")
        (field (name "POWER") "0.0625W")
        (field (name "AUTHOR") "CERN DEM JLC")
      )
      (libsource (lib "") (part "Resistor - 1%_1"))
    )
    (comp (ref "R143")
      (value "10k")
      (footprint "RESC1005X40N")
      (description "Resistor - 1%")
      (fields
        (field (name "PART NUMBER") "R0402_10K_1%_0.0625W_100PPM")
        (field (name "POWER") "0.0625W")
        (field (name "AUTHOR") "CERN DEM JLC")
      )
      (libsource (lib "") (part "Resistor - 1%_1"))
    )
    (comp (ref "R144")
      (value "10k")
      (footprint "RESC1005X40N")
      (description "Resistor - 1%")
      (fields
        (field (name "PART NUMBER") "R0402_10K_1%_0.0625W_100PPM")
        (field (name "POWER") "0.0625W")
        (field (name "AUTHOR") "CERN DEM JLC")
      )
      (libsource (lib "") (part "Resistor - 1%_1"))
    )
    (comp (ref "R145")
      (value "10k")
      (footprint "RESC1005X40N")
      (description "Resistor - 1%")
      (fields
        (field (name "TOLERANCE") "±1%")
        (field (name "PART NUMBER") "R0402_10K_1%_0.0625W_100PPM")
        (field (name "POWER") "0.0625W")
        (field (name "AUTHOR") "CERN DEM JLC")
      )
      (libsource (lib "") (part "Resistor - 1%_1"))
    )
    (comp (ref "R146")
      (value "10k")
      (footprint "RESC1005X40N")
      (description "Resistor - 1%")
      (fields
        (field (name "TOLERANCE") "±1%")
        (field (name "PART NUMBER") "R0402_10K_1%_0.0625W_100PPM")
        (field (name "POWER") "0.0625W")
        (field (name "AUTHOR") "CERN DEM JLC")
      )
      (libsource (lib "") (part "Resistor - 1%_1"))
    )
    (comp (ref "T4")
      (value "BSH103")
      (footprint "SOT95P230X110-3N")
      (description "N-CHANNEL MOSFET WITH DIODE")
      (fields (field (name "MANUFACTURER") "NEXPERIA") (field (name "AUTHOR") "CERN DEM JLC"))
      (libsource (lib "ICs And Semiconductors") (part "N-MOSFET-D 1G 2S 3D"))
    )
    (comp (ref "T5")
      (value "BSH103")
      (footprint "SOT95P230X110-3N")
      (description "N-CHANNEL MOSFET WITH DIODE")
      (fields (field (name "MANUFACTURER") "NEXPERIA") (field (name "AUTHOR") "CERN DEM JLC"))
      (libsource (lib "ICs And Semiconductors") (part "N-MOSFET-D 1G 2S 3D"))
    )
    (comp (ref "T6")
      (value "BSH103")
      (footprint "SOT95P230X110-3N")
      (description "N-CHANNEL MOSFET WITH DIODE")
      (fields (field (name "MANUFACTURER") "NEXPERIA") (field (name "AUTHOR") "CERN DEM JLC"))
      (libsource (lib "ICs And Semiconductors") (part "N-MOSFET-D 1G 2S 3D"))
    )
    (comp (ref "T7")
      (value "BSH103")
      (footprint "SOT95P230X110-3N")
      (description "N-CHANNEL MOSFET WITH DIODE")
      (fields (field (name "MANUFACTURER") "NEXPERIA") (field (name "AUTHOR") "CERN DEM JLC"))
      (libsource (lib "ICs And Semiconductors") (part "N-MOSFET-D 1G 2S 3D"))
    )
    (comp (ref "T8")
      (value "BSH103")
      (footprint "SOT95P230X110-3N")
      (description "N-CHANNEL MOSFET WITH DIODE")
      (fields (field (name "MANUFACTURER") "NEXPERIA") (field (name "AUTHOR") "CERN DEM JLC"))
      (libsource (lib "ICs And Semiconductors") (part "N-MOSFET-D 1G 2S 3D"))
    )
    (comp (ref "T9")
      (value "BSH103")
      (footprint "SOT95P230X110-3N")
      (description "N-CHANNEL MOSFET WITH DIODE")
      (fields (field (name "MANUFACTURER") "NEXPERIA") (field (name "AUTHOR") "CERN DEM JLC"))
      (libsource (lib "ICs And Semiconductors") (part "N-MOSFET-D 1G 2S 3D"))
    )
    (comp (ref "T10")
      (value "BSH103")
      (footprint "SOT95P230X110-3N")
      (description "N-CHANNEL MOSFET WITH DIODE")
      (fields (field (name "MANUFACTURER") "NEXPERIA") (field (name "AUTHOR") "CERN DEM JLC"))
      (libsource (lib "ICs And Semiconductors") (part "N-MOSFET-D 1G 2S 3D"))
    )
    (comp (ref "T11")
      (value "BSH103")
      (footprint "SOT95P230X110-3N")
      (description "N-CHANNEL MOSFET WITH DIODE")
      (fields (field (name "MANUFACTURER") "NEXPERIA") (field (name "AUTHOR") "CERN DEM JLC"))
      (libsource (lib "ICs And Semiconductors") (part "N-MOSFET-D 1G 2S 3D"))
    )
    (comp (ref "T12")
      (value "BSH103")
      (footprint "SOT95P230X110-3N")
      (description "N-CHANNEL MOSFET WITH DIODE")
      (fields (field (name "MANUFACTURER") "NEXPERIA") (field (name "AUTHOR") "CERN DEM JLC"))
      (libsource (lib "ICs And Semiconductors") (part "N-MOSFET-D 1G 2S 3D"))
    )
    (comp (ref "TP2")
      (value "Test Point")
      (footprint "TPS127")
      (fields (field (name "PART NUMBER") "SMD_PAD_1.27X1.27MM") (field (name "AUTHOR") "CERN DEM JLC"))
      (libsource (lib "Eletro-mechanical") (part "Test Point"))
    )
    (comp (ref "TP3")
      (value "Test Point")
      (footprint "TPS127")
      (fields (field (name "PART NUMBER") "SMD_PAD_1.27X1.27MM") (field (name "AUTHOR") "CERN DEM JLC"))
      (libsource (lib "Eletro-mechanical") (part "Test Point"))
    )
  )
  (nets
    (net (code "1") (name "/TEMP_MEAS_AD_DA_REF") (class "Default")
      (node (ref "IC8") (pin "2") (pinfunction "Vo_2") (pintype "output"))
      (node (ref "R61") (pin "1") (pinfunction "1_1") (pintype "passive"))
      (node (ref "R64") (pin "2") (pinfunction "2_2") (pintype "passive"))
      (node (ref "TP2") (pin "1") (pinfunction "1_1") (pintype "bidirectional"))
    )
    (net (code "2") (name "/TEMP_MEAS_DIV_1") (class "Default")
      (node (ref "B5") (pin "1") (pinfunction "1_1") (pintype "bidirectional"))
      (node (ref "R137") (pin "1") (pinfunction "1_1") (pintype "passive"))
      (node (ref "R139") (pin "1") (pinfunction "1_1") (pintype "passive"))
    )
    (net (code "3") (name "/TEMP_MEAS_DIV_2") (class "Default")
      (node (ref "B6") (pin "1") (pinfunction "1_1") (pintype "bidirectional"))
      (node (ref "R138") (pin "1") (pinfunction "1_1") (pintype "passive"))
      (node (ref "R141") (pin "1") (pinfunction "1_1") (pintype "passive"))
    )
    (net (code "4") (name "GND") (class "Default")
      (node (ref "B7") (pin "1") (pinfunction "1_1") (pintype "bidirectional"))
      (node (ref "B8") (pin "1") (pinfunction "1_1") (pintype "bidirectional"))
      (node (ref "C101") (pin "1") (pinfunction "1_1") (pintype "passive"))
      (node (ref "C103") (pin "1") (pinfunction "1_1") (pintype "passive"))
      (node (ref "C104") (pin "1") (pinfunction "1_1") (pintype "passive"))
      (node (ref "C34") (pin "2") (pinfunction "2_2") (pintype "passive"))
      (node (ref "C35") (pin "1") (pinfunction "1_1") (pintype "passive"))
      (node (ref "C36") (pin "1") (pinfunction "1_1") (pintype "passive"))
      (node (ref "C37") (pin "1") (pinfunction "1_1") (pintype "passive"))
      (node (ref "C39") (pin "1") (pinfunction "1_1") (pintype "passive"))
      (node (ref "C41") (pin "1") (pinfunction "1_1") (pintype "passive"))
      (node (ref "C42") (pin "1") (pinfunction "1_1") (pintype "passive"))
      (node (ref "C43") (pin "1") (pinfunction "1_1") (pintype "passive"))
      (node (ref "C44") (pin "1") (pinfunction "1_1") (pintype "passive"))
      (node (ref "C95") (pin "1") (pinfunction "1_1") (pintype "passive"))
      (node (ref "C96") (pin "1") (pinfunction "1_1") (pintype "passive"))
      (node (ref "C97") (pin "1") (pinfunction "1_1") (pintype "passive"))
      (node (ref "C98") (pin "1") (pinfunction "1_1") (pintype "passive"))
      (node (ref "C99") (pin "1") (pinfunction "1_1") (pintype "passive"))
      (node (ref "IC17") (pin "2") (pinfunction "V-_2") (pintype "power_in"))
      (node (ref "IC8") (pin "3") (pinfunction "GND_3") (pintype "power_in"))
      (node (ref "IC9") (pin "4") (pinfunction "V-_4") (pintype "power_in"))
      (node (ref "P2") (pin "1") (pinfunction "CCW_1") (pintype "passive"))
      (node (ref "P2") (pin "2") (pinfunction "W_2") (pintype "passive"))
      (node (ref "P3") (pin "1") (pinfunction "CCW_1") (pintype "passive"))
      (node (ref "P3") (pin "2") (pinfunction "W_2") (pintype "passive"))
      (node (ref "R84") (pin "1") (pinfunction "1_1") (pintype "passive"))
      (node (ref "R85") (pin "1") (pinfunction "1_1") (pintype "passive"))
      (node (ref "R86") (pin "1") (pinfunction "1_1") (pintype "passive"))
      (node (ref "R87") (pin "1") (pinfunction "1_1") (pintype "passive"))
      (node (ref "R88") (pin "1") (pinfunction "1_1") (pintype "passive"))
      (node (ref "R89") (pin "1") (pinfunction "1_1") (pintype "passive"))
      (node (ref "R90") (pin "1") (pinfunction "1_1") (pintype "passive"))
      (node (ref "R91") (pin "1") (pinfunction "1_1") (pintype "passive"))
      (node (ref "R92") (pin "1") (pinfunction "1_1") (pintype "passive"))
      (node (ref "R93") (pin "1") (pinfunction "1_1") (pintype "passive"))
    )
    (net (code "5") (name "Net-(C38-Pad2)") (class "Default")
      (node (ref "C38") (pin "2") (pinfunction "2_2") (pintype "passive"))
      (node (ref "R51") (pin "1") (pinfunction "1_1") (pintype "passive"))
    )
    (net (code "6") (name "Net-(C41-Pad2)") (class "Default")
      (node (ref "C41") (pin "2") (pinfunction "2_2") (pintype "passive"))
      (node (ref "R64") (pin "1") (pinfunction "1_1") (pintype "passive"))
    )
    (net (code "7") (name "Net-(C91-Pad2)") (class "Default")
      (node (ref "C91") (pin "2") (pinfunction "2_2") (pintype "passive"))
      (node (ref "R135") (pin "1") (pinfunction "1_1") (pintype "passive"))
    )
    (net (code "8") (name "Net-(C92-Pad2)") (class "Default")
      (node (ref "C92") (pin "2") (pinfunction "2_2") (pintype "passive"))
      (node (ref "R136") (pin "1") (pinfunction "1_1") (pintype "passive"))
    )
    (net (code "9") (name "Net-(D3A-C)") (class "Default")
      (node (ref "C40") (pin "2") (pinfunction "2_2") (pintype "passive"))
      (node (ref "D3") (pin "1") (pinfunction "C_1") (pintype "passive"))
      (node (ref "D3") (pin "2") (pinfunction "C_2") (pintype "passive"))
      (node (ref "IC17") (pin "1") (pinfunction "OUT_1") (pintype "output"))
      (node (ref "R51") (pin "2") (pinfunction "2_2") (pintype "passive"))
      (node (ref "R63") (pin "1") (pinfunction "1_1") (pintype "passive"))
    )
    (net (code "10") (name "Net-(D3A-COMA)") (class "Default")
      (node (ref "D3") (pin "3") (pinfunction "COMA_3") (pintype "passive"))
      (node (ref "R61") (pin "2") (pinfunction "2_2") (pintype "passive"))
      (node (ref "R62") (pin "1") (pinfunction "1_1") (pintype "passive"))
    )
    (net (code "11") (name "Net-(D8A-C)") (class "Default")
      (node (ref "C93") (pin "2") (pinfunction "2_2") (pintype "passive"))
      (node (ref "D8") (pin "1") (pinfunction "C_1") (pintype "passive"))
      (node (ref "D8") (pin "2") (pinfunction "C_2") (pintype "passive"))
      (node (ref "IC9") (pin "1") (pinfunction "OUT_1") (pintype "output"))
      (node (ref "R135") (pin "2") (pinfunction "2_2") (pintype "passive"))
      (node (ref "R143") (pin "1") (pinfunction "1_1") (pintype "passive"))
    )
    (net (code "12") (name "Net-(D8A-COMA)") (class "Default")
      (node (ref "D8") (pin "3") (pinfunction "COMA_3") (pintype "passive"))
      (node (ref "R139") (pin "2") (pinfunction "2_2") (pintype "passive"))
      (node (ref "R140") (pin "1") (pinfunction "1_1") (pintype "passive"))
    )
    (net (code "13") (name "Net-(D9A-C)") (class "Default")
      (node (ref "C94") (pin "2") (pinfunction "2_2") (pintype "passive"))
      (node (ref "D9") (pin "1") (pinfunction "C_1") (pintype "passive"))
      (node (ref "D9") (pin "2") (pinfunction "C_2") (pintype "passive"))
      (node (ref "IC9") (pin "7") (pinfunction "OUT_7") (pintype "output"))
      (node (ref "R136") (pin "2") (pinfunction "2_2") (pintype "passive"))
      (node (ref "R144") (pin "1") (pinfunction "1_1") (pintype "passive"))
    )
    (net (code "14") (name "Net-(D9A-COMA)") (class "Default")
      (node (ref "D9") (pin "3") (pinfunction "COMA_3") (pintype "passive"))
      (node (ref "R141") (pin "2") (pinfunction "2_2") (pintype "passive"))
      (node (ref "R142") (pin "1") (pinfunction "1_1") (pintype "passive"))
    )
    (net (code "15") (name "Net-(IC9A-IN+)") (class "Default")
      (node (ref "C103") (pin "2") (pinfunction "2_2") (pintype "passive"))
      (node (ref "IC9") (pin "3") (pinfunction "IN+_3") (pintype "input"))
      (node (ref "P2") (pin "3") (pinfunction "CW_3") (pintype "passive"))
      (node (ref "R145") (pin "1") (pinfunction "1_1") (pintype "passive"))
    )
    (net (code "16") (name "Net-(IC9A-IN-)") (class "Default")
      (node (ref "C91") (pin "1") (pinfunction "1_1") (pintype "passive"))
      (node (ref "C93") (pin "1") (pinfunction "1_1") (pintype "passive"))
      (node (ref "IC9") (pin "2") (pinfunction "IN-_2") (pintype "input"))
      (node (ref "R140") (pin "2") (pinfunction "2_2") (pintype "passive"))
    )
    (net (code "17") (name "Net-(IC9B-IN+)") (class "Default")
      (node (ref "C104") (pin "2") (pinfunction "2_2") (pintype "passive"))
      (node (ref "IC9") (pin "5") (pinfunction "IN+_5") (pintype "input"))
      (node (ref "P3") (pin "3") (pinfunction "CW_3") (pintype "passive"))
      (node (ref "R146") (pin "1") (pinfunction "1_1") (pintype "passive"))
    )
    (net (code "18") (name "Net-(IC9B-IN-)") (class "Default")
      (node (ref "C92") (pin "1") (pinfunction "1_1") (pintype "passive"))
      (node (ref "C94") (pin "1") (pinfunction "1_1") (pintype "passive"))
      (node (ref "IC9") (pin "6") (pinfunction "IN-_6") (pintype "input"))
      (node (ref "R142") (pin "2") (pinfunction "2_2") (pintype "passive"))
    )
    (net (code "19") (name "Net-(IC17-IN+)") (class "Default")
      (node (ref "C44") (pin "2") (pinfunction "2_2") (pintype "passive"))
      (node (ref "IC17") (pin "3") (pinfunction "IN+_3") (pintype "input"))
      (node (ref "P1") (pin "1") (pinfunction "CCW_1") (pintype "passive"))
      (node (ref "P1") (pin "2") (pinfunction "W_2") (pintype "passive"))
      (node (ref "R83") (pin "2") (pinfunction "2_2") (pintype "passive"))
    )
    (net (code "20") (name "Net-(IC17-IN-)") (class "Default")
      (node (ref "C38") (pin "1") (pinfunction "1_1") (pintype "passive"))
      (node (ref "C40") (pin "1") (pinfunction "1_1") (pintype "passive"))
      (node (ref "IC17") (pin "4") (pinfunction "IN-_4") (pintype "input"))
      (node (ref "R62") (pin "2") (pinfunction "2_2") (pintype "passive"))
    )
    (net (code "21") (name "Net-(R33-Pad1)") (class "Default")
      (node (ref "R33") (pin "1") (pinfunction "1_1") (pintype "passive"))
      (node (ref "R42") (pin "2") (pinfunction "2_2") (pintype "passive"))
    )
    (net (code "22") (name "Net-(R34-Pad1)") (class "Default")
      (node (ref "R34") (pin "1") (pinfunction "1_1") (pintype "passive"))
      (node (ref "R43") (pin "2") (pinfunction "2_2") (pintype "passive"))
    )
    (net (code "23") (name "Net-(R35-Pad1)") (class "Default")
      (node (ref "R35") (pin "1") (pinfunction "1_1") (pintype "passive"))
      (node (ref "R44") (pin "2") (pinfunction "2_2") (pintype "passive"))
    )
    (net (code "24") (name "Net-(R36-Pad1)") (class "Default")
      (node (ref "R36") (pin "1") (pinfunction "1_1") (pintype "passive"))
      (node (ref "R45") (pin "2") (pinfunction "2_2") (pintype "passive"))
    )
    (net (code "25") (name "Net-(R37-Pad1)") (class "Default")
      (node (ref "R37") (pin "1") (pinfunction "1_1") (pintype "passive"))
      (node (ref "R46") (pin "2") (pinfunction "2_2") (pintype "passive"))
    )
    (net (code "26") (name "Net-(R38-Pad1)") (class "Default")
      (node (ref "R38") (pin "1") (pinfunction "1_1") (pintype "passive"))
      (node (ref "R47") (pin "2") (pinfunction "2_2") (pintype "passive"))
    )
    (net (code "27") (name "Net-(R39-Pad1)") (class "Default")
      (node (ref "R39") (pin "1") (pinfunction "1_1") (pintype "passive"))
      (node (ref "R48") (pin "2") (pinfunction "2_2") (pintype "passive"))
    )
    (net (code "28") (name "Net-(R40-Pad1)") (class "Default")
      (node (ref "R40") (pin "1") (pinfunction "1_1") (pintype "passive"))
      (node (ref "R49") (pin "2") (pinfunction "2_2") (pintype "passive"))
    )
    (net (code "29") (name "Net-(R41-Pad1)") (class "Default")
      (node (ref "R41") (pin "1") (pinfunction "1_1") (pintype "passive"))
      (node (ref "R50") (pin "2") (pinfunction "2_2") (pintype "passive"))
    )
    (net (code "30") (name "Net-(R42-Pad1)") (class "Default")
      (node (ref "R42") (pin "1") (pinfunction "1_1") (pintype "passive"))
      (node (ref "R52") (pin "2") (pinfunction "2_2") (pintype "passive"))
    )
    (net (code "31") (name "Net-(R43-Pad1)") (class "Default")
      (node (ref "R43") (pin "1") (pinfunction "1_1") (pintype "passive"))
      (node (ref "R53") (pin "2") (pinfunction "2_2") (pintype "passive"))
    )
    (net (code "32") (name "Net-(R44-Pad1)") (class "Default")
      (node (ref "R44") (pin "1") (pinfunction "1_1") (pintype "passive"))
      (node (ref "R54") (pin "2") (pinfunction "2_2") (pintype "passive"))
    )
    (net (code "33") (name "Net-(R45-Pad1)") (class "Default")
      (node (ref "R45") (pin "1") (pinfunction "1_1") (pintype "passive"))
      (node (ref "R55") (pin "2") (pinfunction "2_2") (pintype "passive"))
    )
    (net (code "34") (name "Net-(R46-Pad1)") (class "Default")
      (node (ref "R46") (pin "1") (pinfunction "1_1") (pintype "passive"))
      (node (ref "R56") (pin "2") (pinfunction "2_2") (pintype "passive"))
    )
    (net (code "35") (name "Net-(R47-Pad1)") (class "Default")
      (node (ref "R47") (pin "1") (pinfunction "1_1") (pintype "passive"))
      (node (ref "R57") (pin "2") (pinfunction "2_2") (pintype "passive"))
    )
    (net (code "36") (name "Net-(R48-Pad1)") (class "Default")
      (node (ref "R48") (pin "1") (pinfunction "1_1") (pintype "passive"))
      (node (ref "R58") (pin "2") (pinfunction "2_2") (pintype "passive"))
    )
    (net (code "37") (name "Net-(R49-Pad1)") (class "Default")
      (node (ref "R49") (pin "1") (pinfunction "1_1") (pintype "passive"))
      (node (ref "R59") (pin "2") (pinfunction "2_2") (pintype "passive"))
    )
    (net (code "38") (name "Net-(R50-Pad1)") (class "Default")
      (node (ref "R50") (pin "1") (pinfunction "1_1") (pintype "passive"))
      (node (ref "R60") (pin "2") (pinfunction "2_2") (pintype "passive"))
    )
    (net (code "39") (name "Net-(R65-Pad1)") (class "Default")
      (node (ref "R65") (pin "1") (pinfunction "1_1") (pintype "passive"))
      (node (ref "R74") (pin "2") (pinfunction "2_2") (pintype "passive"))
    )
    (net (code "40") (name "Net-(R66-Pad1)") (class "Default")
      (node (ref "R66") (pin "1") (pinfunction "1_1") (pintype "passive"))
      (node (ref "R75") (pin "2") (pinfunction "2_2") (pintype "passive"))
    )
    (net (code "41") (name "Net-(R67-Pad1)") (class "Default")
      (node (ref "R67") (pin "1") (pinfunction "1_1") (pintype "passive"))
      (node (ref "R76") (pin "2") (pinfunction "2_2") (pintype "passive"))
    )
    (net (code "42") (name "Net-(R68-Pad1)") (class "Default")
      (node (ref "R68") (pin "1") (pinfunction "1_1") (pintype "passive"))
      (node (ref "R77") (pin "2") (pinfunction "2_2") (pintype "passive"))
    )
    (net (code "43") (name "Net-(R69-Pad1)") (class "Default")
      (node (ref "R69") (pin "1") (pinfunction "1_1") (pintype "passive"))
      (node (ref "R78") (pin "2") (pinfunction "2_2") (pintype "passive"))
    )
    (net (code "44") (name "Net-(R70-Pad1)") (class "Default")
      (node (ref "R70") (pin "1") (pinfunction "1_1") (pintype "passive"))
      (node (ref "R79") (pin "2") (pinfunction "2_2") (pintype "passive"))
    )
    (net (code "45") (name "Net-(R71-Pad1)") (class "Default")
      (node (ref "R71") (pin "1") (pinfunction "1_1") (pintype "passive"))
      (node (ref "R80") (pin "2") (pinfunction "2_2") (pintype "passive"))
    )
    (net (code "46") (name "Net-(R72-Pad1)") (class "Default")
      (node (ref "R72") (pin "1") (pinfunction "1_1") (pintype "passive"))
      (node (ref "R81") (pin "2") (pinfunction "2_2") (pintype "passive"))
    )
    (net (code "47") (name "Net-(R73-Pad1)") (class "Default")
      (node (ref "R73") (pin "1") (pinfunction "1_1") (pintype "passive"))
      (node (ref "R82") (pin "2") (pinfunction "2_2") (pintype "passive"))
    )
    (net (code "48") (name "Net-(R74-Pad1)") (class "Default")
      (node (ref "R74") (pin "1") (pinfunction "1_1") (pintype "passive"))
      (node (ref "R84") (pin "2") (pinfunction "2_2") (pintype "passive"))
    )
    (net (code "49") (name "Net-(R75-Pad1)") (class "Default")
      (node (ref "R75") (pin "1") (pinfunction "1_1") (pintype "passive"))
      (node (ref "R85") (pin "2") (pinfunction "2_2") (pintype "passive"))
    )
    (net (code "50") (name "Net-(R76-Pad1)") (class "Default")
      (node (ref "R76") (pin "1") (pinfunction "1_1") (pintype "passive"))
      (node (ref "R86") (pin "2") (pinfunction "2_2") (pintype "passive"))
    )
    (net (code "51") (name "Net-(R77-Pad1)") (class "Default")
      (node (ref "R77") (pin "1") (pinfunction "1_1") (pintype "passive"))
      (node (ref "R87") (pin "2") (pinfunction "2_2") (pintype "passive"))
    )
    (net (code "52") (name "Net-(R78-Pad1)") (class "Default")
      (node (ref "R78") (pin "1") (pinfunction "1_1") (pintype "passive"))
      (node (ref "R88") (pin "2") (pinfunction "2_2") (pintype "passive"))
    )
    (net (code "53") (name "Net-(R79-Pad1)") (class "Default")
      (node (ref "R79") (pin "1") (pinfunction "1_1") (pintype "passive"))
      (node (ref "R89") (pin "2") (pinfunction "2_2") (pintype "passive"))
    )
    (net (code "54") (name "Net-(R80-Pad1)") (class "Default")
      (node (ref "R80") (pin "1") (pinfunction "1_1") (pintype "passive"))
      (node (ref "R90") (pin "2") (pinfunction "2_2") (pintype "passive"))
    )
    (net (code "55") (name "Net-(R81-Pad1)") (class "Default")
      (node (ref "R81") (pin "1") (pinfunction "1_1") (pintype "passive"))
      (node (ref "R91") (pin "2") (pinfunction "2_2") (pintype "passive"))
    )
    (net (code "56") (name "Net-(R82-Pad1)") (class "Default")
      (node (ref "R82") (pin "1") (pinfunction "1_1") (pintype "passive"))
      (node (ref "R92") (pin "2") (pinfunction "2_2") (pintype "passive"))
    )
    (net (code "57") (name "Net-(R83-Pad1)") (class "Default")
      (node (ref "R83") (pin "1") (pinfunction "1_1") (pintype "passive"))
      (node (ref "R93") (pin "2") (pinfunction "2_2") (pintype "passive"))
    )
    (net (code "58") (name "Net-(T4-D)") (class "Default")
      (node (ref "R52") (pin "1") (pinfunction "1_1") (pintype "passive"))
      (node (ref "T4") (pin "3") (pinfunction "D_3") (pintype "passive"))
    )
    (net (code "59") (name "Net-(T4-G)") (class "Default")
      (node (ref "R63") (pin "2") (pinfunction "2_2") (pintype "passive"))
      (node (ref "T4") (pin "1") (pinfunction "G_1") (pintype "passive"))
      (node (ref "T5") (pin "1") (pinfunction "G_1") (pintype "passive"))
      (node (ref "T6") (pin "1") (pinfunction "G_1") (pintype "passive"))
      (node (ref "T7") (pin "1") (pinfunction "G_1") (pintype "passive"))
      (node (ref "T8") (pin "1") (pinfunction "G_1") (pintype "passive"))
      (node (ref "TP3") (pin "1") (pinfunction "1_1") (pintype "bidirectional"))
    )
    (net (code "60") (name "Net-(T4-S)") (class "Default")
      (node (ref "R65") (pin "2") (pinfunction "2_2") (pintype "passive"))
      (node (ref "T4") (pin "2") (pinfunction "S_2") (pintype "passive"))
    )
    (net (code "61") (name "Net-(T5-D)") (class "Default")
      (node (ref "R53") (pin "1") (pinfunction "1_1") (pintype "passive"))
      (node (ref "T5") (pin "3") (pinfunction "D_3") (pintype "passive"))
    )
    (net (code "62") (name "Net-(T5-S)") (class "Default")
      (node (ref "R66") (pin "2") (pinfunction "2_2") (pintype "passive"))
      (node (ref "T5") (pin "2") (pinfunction "S_2") (pintype "passive"))
    )
    (net (code "63") (name "Net-(T6-D)") (class "Default")
      (node (ref "R54") (pin "1") (pinfunction "1_1") (pintype "passive"))
      (node (ref "T6") (pin "3") (pinfunction "D_3") (pintype "passive"))
    )
    (net (code "64") (name "Net-(T6-S)") (class "Default")
      (node (ref "R67") (pin "2") (pinfunction "2_2") (pintype "passive"))
      (node (ref "T6") (pin "2") (pinfunction "S_2") (pintype "passive"))
    )
    (net (code "65") (name "Net-(T7-D)") (class "Default")
      (node (ref "R55") (pin "1") (pinfunction "1_1") (pintype "passive"))
      (node (ref "T7") (pin "3") (pinfunction "D_3") (pintype "passive"))
    )
    (net (code "66") (name "Net-(T7-S)") (class "Default")
      (node (ref "R68") (pin "2") (pinfunction "2_2") (pintype "passive"))
      (node (ref "T7") (pin "2") (pinfunction "S_2") (pintype "passive"))
    )
    (net (code "67") (name "Net-(T8-D)") (class "Default")
      (node (ref "R56") (pin "1") (pinfunction "1_1") (pintype "passive"))
      (node (ref "T8") (pin "3") (pinfunction "D_3") (pintype "passive"))
    )
    (net (code "68") (name "Net-(T8-S)") (class "Default")
      (node (ref "R69") (pin "2") (pinfunction "2_2") (pintype "passive"))
      (node (ref "T8") (pin "2") (pinfunction "S_2") (pintype "passive"))
    )
    (net (code "69") (name "Net-(T9-D)") (class "Default")
      (node (ref "R57") (pin "1") (pinfunction "1_1") (pintype "passive"))
      (node (ref "T9") (pin "3") (pinfunction "D_3") (pintype "passive"))
    )
    (net (code "70") (name "Net-(T9-S)") (class "Default")
      (node (ref "R70") (pin "2") (pinfunction "2_2") (pintype "passive"))
      (node (ref "T9") (pin "2") (pinfunction "S_2") (pintype "passive"))
    )
    (net (code "71") (name "Net-(T10-D)") (class "Default")
      (node (ref "R58") (pin "1") (pinfunction "1_1") (pintype "passive"))
      (node (ref "T10") (pin "3") (pinfunction "D_3") (pintype "passive"))
    )
    (net (code "72") (name "Net-(T10-G)") (class "Default")
      (node (ref "R143") (pin "2") (pinfunction "2_2") (pintype "passive"))
      (node (ref "T10") (pin "1") (pinfunction "G_1") (pintype "passive"))
      (node (ref "T9") (pin "1") (pinfunction "G_1") (pintype "passive"))
    )
    (net (code "73") (name "Net-(T10-S)") (class "Default")
      (node (ref "R71") (pin "2") (pinfunction "2_2") (pintype "passive"))
      (node (ref "T10") (pin "2") (pinfunction "S_2") (pintype "passive"))
    )
    (net (code "74") (name "Net-(T11-D)") (class "Default")
      (node (ref "R59") (pin "1") (pinfunction "1_1") (pintype "passive"))
      (node (ref "T11") (pin "3") (pinfunction "D_3") (pintype "passive"))
    )
    (net (code "75") (name "Net-(T11-G)") (class "Default")
      (node (ref "R144") (pin "2") (pinfunction "2_2") (pintype "passive"))
      (node (ref "T11") (pin "1") (pinfunction "G_1") (pintype "passive"))
      (node (ref "T12") (pin "1") (pinfunction "G_1") (pintype "passive"))
    )
    (net (code "76") (name "Net-(T11-S)") (class "Default")
      (node (ref "R72") (pin "2") (pinfunction "2_2") (pintype "passive"))
      (node (ref "T11") (pin "2") (pinfunction "S_2") (pintype "passive"))
    )
    (net (code "77") (name "Net-(T12-D)") (class "Default")
      (node (ref "R60") (pin "1") (pinfunction "1_1") (pintype "passive"))
      (node (ref "T12") (pin "3") (pinfunction "D_3") (pintype "passive"))
    )
    (net (code "78") (name "Net-(T12-S)") (class "Default")
      (node (ref "R73") (pin "2") (pinfunction "2_2") (pintype "passive"))
      (node (ref "T12") (pin "2") (pinfunction "S_2") (pintype "passive"))
    )
    (net (code "79") (name "P5V0A") (class "Default")
      (node (ref "C37") (pin "2") (pinfunction "2_2") (pintype "passive"))
      (node (ref "C39") (pin "2") (pinfunction "2_2") (pintype "passive"))
      (node (ref "C95") (pin "2") (pinfunction "2_2") (pintype "passive"))
      (node (ref "C96") (pin "2") (pinfunction "2_2") (pintype "passive"))
      (node (ref "C97") (pin "2") (pinfunction "2_2") (pintype "passive"))
      (node (ref "C98") (pin "2") (pinfunction "2_2") (pintype "passive"))
      (node (ref "IC8") (pin "1") (pinfunction "+Vs_1") (pintype "power_in"))
      (node (ref "R137") (pin "2") (pinfunction "2_2") (pintype "passive"))
      (node (ref "R138") (pin "2") (pinfunction "2_2") (pintype "passive"))
    )
    (net (code "80") (name "P12V0") (class "Default")
      (node (ref "C101") (pin "2") (pinfunction "2_2") (pintype "passive"))
      (node (ref "C42") (pin "2") (pinfunction "2_2") (pintype "passive"))
      (node (ref "C43") (pin "2") (pinfunction "2_2") (pintype "passive"))
      (node (ref "C99") (pin "2") (pinfunction "2_2") (pintype "passive"))
      (node (ref "IC17") (pin "5") (pinfunction "V+_5") (pintype "power_in"))
      (node (ref "IC9") (pin "8") (pinfunction "V+_8") (pintype "power_in"))
      (node (ref "L8") (pin "1") (pinfunction "1_1") (pintype "passive"))
    )
    (net (code "81") (name "P12V0_HEAT") (class "Default")
      (node (ref "C34") (pin "1") (pinfunction "1_1") (pintype "passive"))
      (node (ref "C35") (pin "2") (pinfunction "2_2") (pintype "passive"))
      (node (ref "C36") (pin "2") (pinfunction "2_2") (pintype "passive"))
      (node (ref "L8") (pin "2") (pinfunction "2_2") (pintype "passive"))
      (node (ref "R33") (pin "2") (pinfunction "2_2") (pintype "passive"))
      (node (ref "R34") (pin "2") (pinfunction "2_2") (pintype "passive"))
      (node (ref "R35") (pin "2") (pinfunction "2_2") (pintype "passive"))
      (node (ref "R36") (pin "2") (pinfunction "2_2") (pintype "passive"))
      (node (ref "R37") (pin "2") (pinfunction "2_2") (pintype "passive"))
      (node (ref "R38") (pin "2") (pinfunction "2_2") (pintype "passive"))
      (node (ref "R39") (pin "2") (pinfunction "2_2") (pintype "passive"))
      (node (ref "R40") (pin "2") (pinfunction "2_2") (pintype "passive"))
      (node (ref "R41") (pin "2") (pinfunction "2_2") (pintype "passive"))
    )
    (net (code "82") (name "VREF_P5V0") (class "Default")
      (node (ref "P1") (pin "3") (pinfunction "CW_3") (pintype "passive"))
      (node (ref "R145") (pin "2") (pinfunction "2_2") (pintype "passive"))
      (node (ref "R146") (pin "2") (pinfunction "2_2") (pintype "passive"))
    )
  )
)
